# PWR.net
KiCad netlist of a schematic drawn in Altium Designer
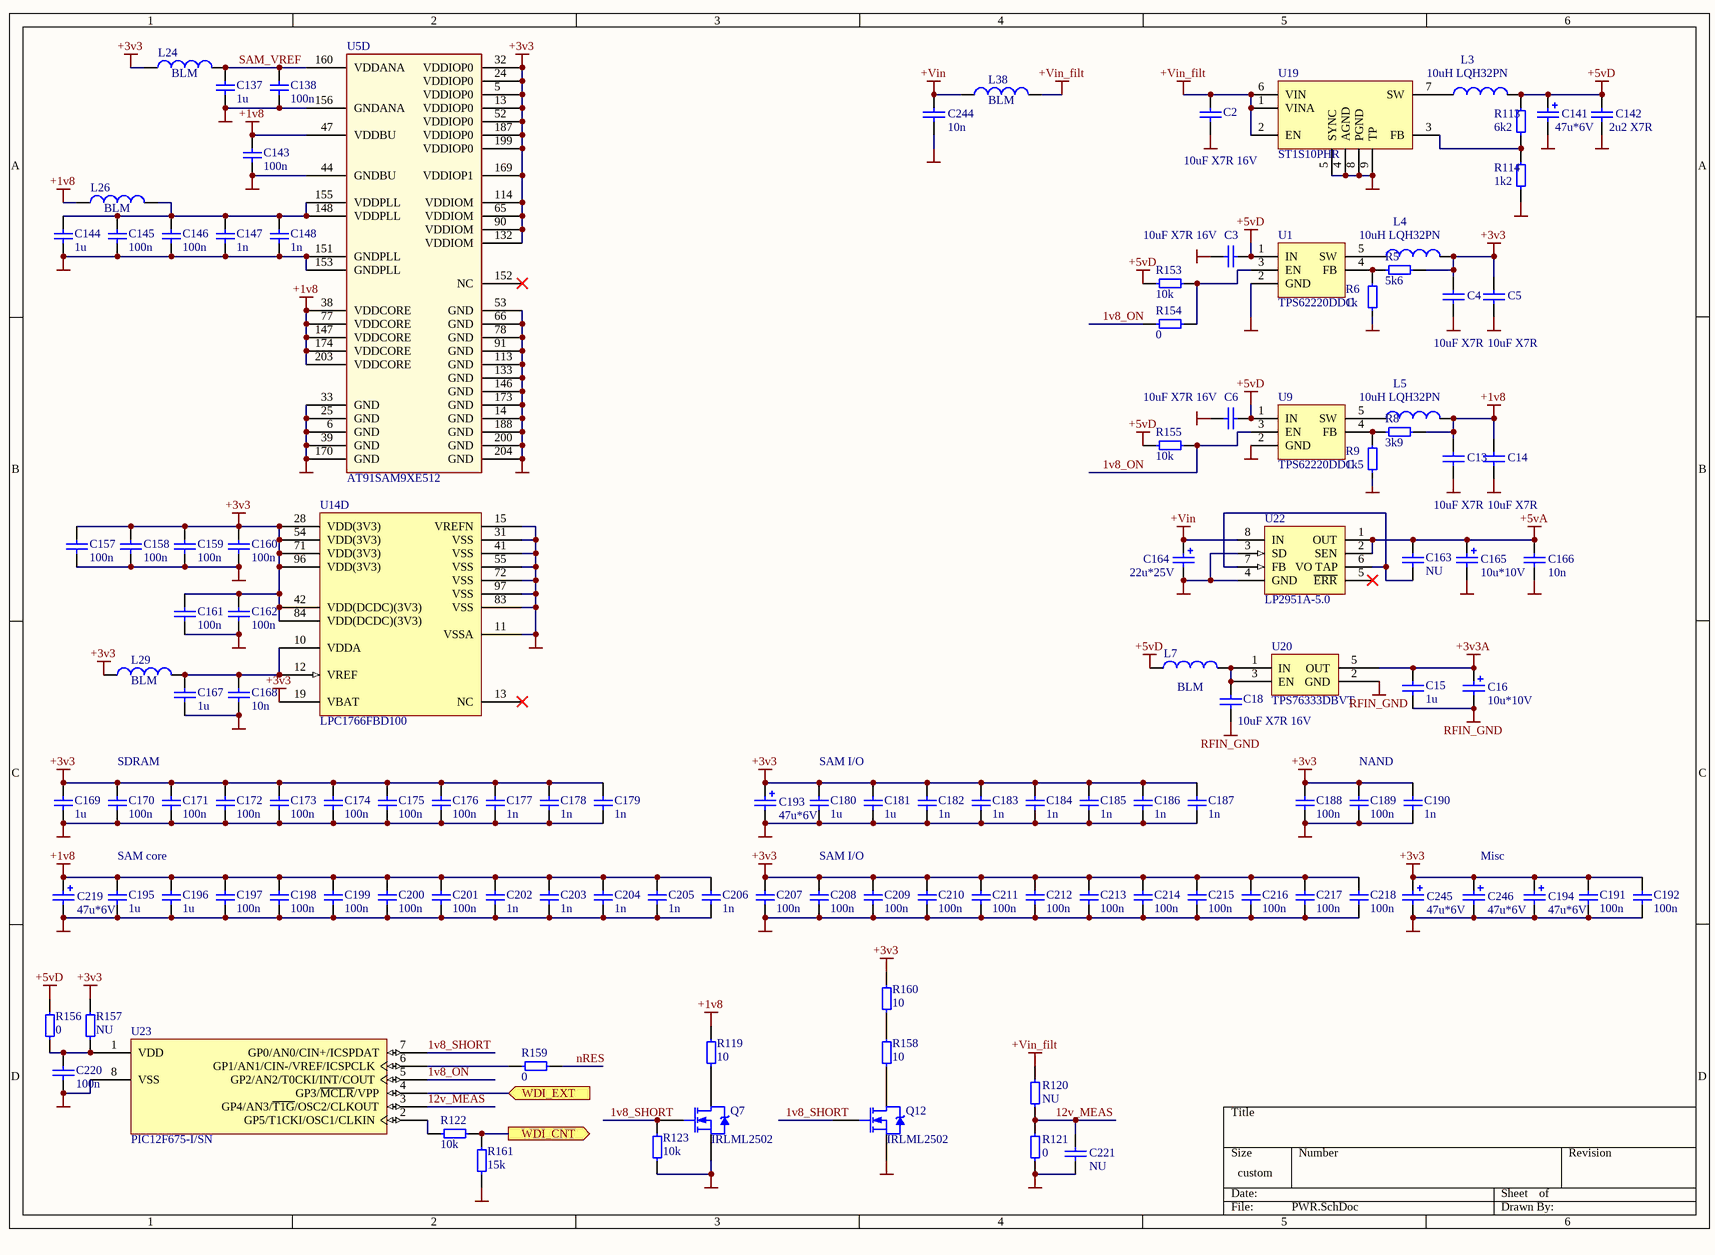
[diagram p0: PWR.SchDoc]

(export (version "E")
  (design (tool "Eeschema 10.0.6"))
  (components
    (comp (ref "C2")
      (value "10uF X7R 16V")
      (footprint "CAPC3216M")
      (description "Capacitor")
      (fields (field (name "PUBLISHER") "Altium Limited"))
      (libsource (lib "") (part "Cap_1"))
    )
    (comp (ref "C3")
      (value "10uF X7R 16V")
      (footprint "CAPC3216M")
      (description "Capacitor")
      (fields (field (name "PUBLISHER") "Altium Limited"))
      (libsource (lib "") (part "Cap_1"))
    )
    (comp (ref "C4")
      (value "10uF X7R")
      (footprint "CAPC3216M")
      (description "Capacitor")
      (fields (field (name "PUBLISHER") "Altium Limited"))
      (libsource (lib "") (part "Cap_1"))
    )
    (comp (ref "C5")
      (value "10uF X7R")
      (footprint "CAPC3216M")
      (description "Capacitor")
      (fields (field (name "PUBLISHER") "Altium Limited"))
      (libsource (lib "") (part "Cap_1"))
    )
    (comp (ref "C6")
      (value "10uF X7R 16V")
      (footprint "CAPC3216M")
      (description "Capacitor")
      (fields (field (name "PUBLISHER") "Altium Limited"))
      (libsource (lib "") (part "Cap_1"))
    )
    (comp (ref "C13")
      (value "10uF X7R")
      (footprint "CAPC3216M")
      (description "Capacitor")
      (fields (field (name "PUBLISHER") "Altium Limited"))
      (libsource (lib "") (part "Cap_1"))
    )
    (comp (ref "C14")
      (value "10uF X7R")
      (footprint "CAPC3216M")
      (description "Capacitor")
      (fields (field (name "PUBLISHER") "Altium Limited"))
      (libsource (lib "") (part "Cap_1"))
    )
    (comp (ref "C15")
      (value "1u")
      (footprint "CAPC2012L")
      (description "Capacitor")
      (fields (field (name "PUBLISHER") "Altium Limited"))
      (libsource (lib "") (part "Cap_1"))
    )
    (comp (ref "C16")
      (value "10u*10V")
      (footprint "Case_A")
      (description "Polarized Capacitor (Surface Mount)")
      (fields (field (name "PUBLISHER") "Altium Limited"))
      (libsource (lib "Sch components") (part "Cap Pol"))
    )
    (comp (ref "C18")
      (value "10uF X7R 16V")
      (footprint "CAPC3216M")
      (description "Capacitor")
      (fields (field (name "PUBLISHER") "Altium Limited"))
      (libsource (lib "") (part "Cap_1"))
    )
    (comp (ref "C137")
      (value "1u")
      (footprint "CAPC2012L")
      (description "Capacitor")
      (fields (field (name "PUBLISHER") "Altium Limited"))
      (libsource (lib "Sch components") (part "Cap"))
    )
    (comp (ref "C138")
      (value "100n")
      (footprint "CAPC1608L")
      (description "Capacitor")
      (fields (field (name "PUBLISHER") "Altium Limited"))
      (libsource (lib "Sch components") (part "Cap"))
    )
    (comp (ref "C141")
      (value "47u*6V")
      (footprint "Case_A")
      (description "Polarized Capacitor (Surface Mount)")
      (fields (field (name "PUBLISHER") "Altium Limited"))
      (libsource (lib "Sch components") (part "Cap Pol"))
    )
    (comp (ref "C142")
      (value "2u2 X7R")
      (footprint "CAPC2012N")
      (description "Capacitor")
      (fields (field (name "PUBLISHER") "Altium Limited"))
      (libsource (lib "") (part "Cap_1"))
    )
    (comp (ref "C143")
      (value "100n")
      (footprint "CAPC1608L")
      (description "Capacitor")
      (fields (field (name "PUBLISHER") "Altium Limited"))
      (libsource (lib "Sch components") (part "Cap"))
    )
    (comp (ref "C144")
      (value "1u")
      (footprint "CAPC2012L")
      (description "Capacitor")
      (fields (field (name "PUBLISHER") "Altium Limited"))
      (libsource (lib "Sch components") (part "Cap"))
    )
    (comp (ref "C145")
      (value "100n")
      (footprint "CAPC1608L")
      (description "Capacitor")
      (fields (field (name "PUBLISHER") "Altium Limited"))
      (libsource (lib "Sch components") (part "Cap"))
    )
    (comp (ref "C146")
      (value "100n")
      (footprint "CAPC1608L")
      (description "Capacitor")
      (fields (field (name "PUBLISHER") "Altium Limited"))
      (libsource (lib "Sch components") (part "Cap"))
    )
    (comp (ref "C147")
      (value "1n")
      (footprint "CAPC1608L")
      (description "Capacitor")
      (fields (field (name "PUBLISHER") "Altium Limited"))
      (libsource (lib "Sch components") (part "Cap"))
    )
    (comp (ref "C148")
      (value "1n")
      (footprint "CAPC1608L")
      (description "Capacitor")
      (fields (field (name "PUBLISHER") "Altium Limited"))
      (libsource (lib "Sch components") (part "Cap"))
    )
    (comp (ref "C157")
      (value "100n")
      (footprint "CAPC1608N")
      (description "Capacitor")
      (fields (field (name "PUBLISHER") "Altium Limited"))
      (libsource (lib "") (part "Cap_1"))
    )
    (comp (ref "C158")
      (value "100n")
      (footprint "CAPC1608N")
      (description "Capacitor")
      (fields (field (name "PUBLISHER") "Altium Limited"))
      (libsource (lib "") (part "Cap_1"))
    )
    (comp (ref "C159")
      (value "100n")
      (footprint "CAPC1608N")
      (description "Capacitor")
      (fields (field (name "PUBLISHER") "Altium Limited"))
      (libsource (lib "") (part "Cap_1"))
    )
    (comp (ref "C160")
      (value "100n")
      (footprint "CAPC1608N")
      (description "Capacitor")
      (fields (field (name "PUBLISHER") "Altium Limited"))
      (libsource (lib "") (part "Cap_1"))
    )
    (comp (ref "C161")
      (value "100n")
      (footprint "CAPC1608N")
      (description "Capacitor")
      (fields (field (name "PUBLISHER") "Altium Limited"))
      (libsource (lib "") (part "Cap_1"))
    )
    (comp (ref "C162")
      (value "100n")
      (footprint "CAPC1608N")
      (description "Capacitor")
      (fields (field (name "PUBLISHER") "Altium Limited"))
      (libsource (lib "") (part "Cap_1"))
    )
    (comp (ref "C163")
      (value "NU")
      (footprint "CAPC1608N")
      (description "Capacitor")
      (fields (field (name "PUBLISHER") "Altium Limited"))
      (libsource (lib "") (part "Cap_1"))
    )
    (comp (ref "C164")
      (value "22u*25V")
      (footprint "Case_D")
      (description "Polarized Capacitor (Surface Mount)")
      (fields (field (name "PUBLISHER") "Altium Limited"))
      (libsource (lib "Sch components") (part "Cap Pol"))
    )
    (comp (ref "C165")
      (value "10u*10V")
      (footprint "Case_A")
      (description "Polarized Capacitor (Surface Mount)")
      (fields (field (name "PUBLISHER") "Altium Limited"))
      (libsource (lib "Sch components") (part "Cap Pol"))
    )
    (comp (ref "C166")
      (value "10n")
      (footprint "CAPC1608N")
      (description "Capacitor")
      (fields (field (name "PUBLISHER") "Altium Limited"))
      (libsource (lib "") (part "Cap_1"))
    )
    (comp (ref "C167")
      (value "1u")
      (footprint "CAPC2012L")
      (description "Capacitor")
      (fields (field (name "PUBLISHER") "Altium Limited"))
      (libsource (lib "") (part "Cap_1"))
    )
    (comp (ref "C168")
      (value "10n")
      (footprint "CAPC1608N")
      (description "Capacitor")
      (fields (field (name "PUBLISHER") "Altium Limited"))
      (libsource (lib "") (part "Cap_1"))
    )
    (comp (ref "C169")
      (value "1u")
      (footprint "CAPC2012L")
      (description "Capacitor")
      (fields (field (name "PUBLISHER") "Altium Limited"))
      (libsource (lib "Sch components") (part "Cap"))
    )
    (comp (ref "C170")
      (value "100n")
      (footprint "CAPC1608L")
      (description "Capacitor")
      (fields (field (name "PUBLISHER") "Altium Limited"))
      (libsource (lib "Sch components") (part "Cap"))
    )
    (comp (ref "C171")
      (value "100n")
      (footprint "CAPC1608L")
      (description "Capacitor")
      (fields (field (name "PUBLISHER") "Altium Limited"))
      (libsource (lib "Sch components") (part "Cap"))
    )
    (comp (ref "C172")
      (value "100n")
      (footprint "CAPC1608L")
      (description "Capacitor")
      (fields (field (name "PUBLISHER") "Altium Limited"))
      (libsource (lib "Sch components") (part "Cap"))
    )
    (comp (ref "C173")
      (value "100n")
      (footprint "CAPC1608L")
      (description "Capacitor")
      (fields (field (name "PUBLISHER") "Altium Limited"))
      (libsource (lib "Sch components") (part "Cap"))
    )
    (comp (ref "C174")
      (value "100n")
      (footprint "CAPC1608L")
      (description "Capacitor")
      (fields (field (name "PUBLISHER") "Altium Limited"))
      (libsource (lib "Sch components") (part "Cap"))
    )
    (comp (ref "C175")
      (value "100n")
      (footprint "CAPC1608L")
      (description "Capacitor")
      (fields (field (name "PUBLISHER") "Altium Limited"))
      (libsource (lib "Sch components") (part "Cap"))
    )
    (comp (ref "C176")
      (value "100n")
      (footprint "CAPC1608L")
      (description "Capacitor")
      (fields (field (name "PUBLISHER") "Altium Limited"))
      (libsource (lib "Sch components") (part "Cap"))
    )
    (comp (ref "C177")
      (value "1n")
      (footprint "CAPC1608L")
      (description "Capacitor")
      (fields (field (name "PUBLISHER") "Altium Limited"))
      (libsource (lib "Sch components") (part "Cap"))
    )
    (comp (ref "C178")
      (value "1n")
      (footprint "CAPC1608L")
      (description "Capacitor")
      (fields (field (name "PUBLISHER") "Altium Limited"))
      (libsource (lib "Sch components") (part "Cap"))
    )
    (comp (ref "C179")
      (value "1n")
      (footprint "CAPC1608L")
      (description "Capacitor")
      (fields (field (name "PUBLISHER") "Altium Limited"))
      (libsource (lib "Sch components") (part "Cap"))
    )
    (comp (ref "C180")
      (value "1u")
      (footprint "CAPC2012L")
      (description "Capacitor")
      (fields (field (name "PUBLISHER") "Altium Limited"))
      (libsource (lib "Sch components") (part "Cap"))
    )
    (comp (ref "C181")
      (value "1u")
      (footprint "CAPC2012L")
      (description "Capacitor")
      (fields (field (name "PUBLISHER") "Altium Limited"))
      (libsource (lib "Sch components") (part "Cap"))
    )
    (comp (ref "C182")
      (value "1n")
      (footprint "CAPC1608L")
      (description "Capacitor")
      (fields (field (name "PUBLISHER") "Altium Limited"))
      (libsource (lib "Sch components") (part "Cap"))
    )
    (comp (ref "C183")
      (value "1n")
      (footprint "CAPC1608L")
      (description "Capacitor")
      (fields (field (name "PUBLISHER") "Altium Limited"))
      (libsource (lib "Sch components") (part "Cap"))
    )
    (comp (ref "C184")
      (value "1n")
      (footprint "CAPC1608L")
      (description "Capacitor")
      (fields (field (name "PUBLISHER") "Altium Limited"))
      (libsource (lib "Sch components") (part "Cap"))
    )
    (comp (ref "C185")
      (value "1n")
      (footprint "CAPC1608L")
      (description "Capacitor")
      (fields (field (name "PUBLISHER") "Altium Limited"))
      (libsource (lib "Sch components") (part "Cap"))
    )
    (comp (ref "C186")
      (value "1n")
      (footprint "CAPC1608L")
      (description "Capacitor")
      (fields (field (name "PUBLISHER") "Altium Limited"))
      (libsource (lib "Sch components") (part "Cap"))
    )
    (comp (ref "C187")
      (value "1n")
      (footprint "CAPC1608L")
      (description "Capacitor")
      (fields (field (name "PUBLISHER") "Altium Limited"))
      (libsource (lib "Sch components") (part "Cap"))
    )
    (comp (ref "C188")
      (value "100n")
      (footprint "CAPC1608L")
      (description "Capacitor")
      (fields (field (name "PUBLISHER") "Altium Limited"))
      (libsource (lib "Sch components") (part "Cap"))
    )
    (comp (ref "C189")
      (value "100n")
      (footprint "CAPC1608L")
      (description "Capacitor")
      (fields (field (name "PUBLISHER") "Altium Limited"))
      (libsource (lib "Sch components") (part "Cap"))
    )
    (comp (ref "C190")
      (value "1n")
      (footprint "CAPC1608L")
      (description "Capacitor")
      (fields (field (name "PUBLISHER") "Altium Limited"))
      (libsource (lib "Sch components") (part "Cap"))
    )
    (comp (ref "C191")
      (value "100n")
      (footprint "CAPC1608L")
      (description "Capacitor")
      (fields (field (name "PUBLISHER") "Altium Limited"))
      (libsource (lib "Sch components") (part "Cap"))
    )
    (comp (ref "C192")
      (value "100n")
      (footprint "CAPC1608L")
      (description "Capacitor")
      (fields (field (name "PUBLISHER") "Altium Limited"))
      (libsource (lib "Sch components") (part "Cap"))
    )
    (comp (ref "C193")
      (value "47u*6V")
      (footprint "Case_A")
      (description "Polarized Capacitor (Surface Mount)")
      (fields (field (name "PUBLISHER") "Altium Limited"))
      (libsource (lib "Sch components") (part "Cap Pol"))
    )
    (comp (ref "C194")
      (value "47u*6V")
      (footprint "Case_A")
      (description "Polarized Capacitor (Surface Mount)")
      (fields (field (name "PUBLISHER") "Altium Limited"))
      (libsource (lib "Sch components") (part "Cap Pol"))
    )
    (comp (ref "C195")
      (value "1u")
      (footprint "CAPC2012L")
      (description "Capacitor")
      (fields (field (name "PUBLISHER") "Altium Limited"))
      (libsource (lib "Sch components") (part "Cap"))
    )
    (comp (ref "C196")
      (value "1u")
      (footprint "CAPC2012L")
      (description "Capacitor")
      (fields (field (name "PUBLISHER") "Altium Limited"))
      (libsource (lib "Sch components") (part "Cap"))
    )
    (comp (ref "C197")
      (value "100n")
      (footprint "CAPC1608L")
      (description "Capacitor")
      (fields (field (name "PUBLISHER") "Altium Limited"))
      (libsource (lib "Sch components") (part "Cap"))
    )
    (comp (ref "C198")
      (value "100n")
      (footprint "CAPC1608L")
      (description "Capacitor")
      (fields (field (name "PUBLISHER") "Altium Limited"))
      (libsource (lib "Sch components") (part "Cap"))
    )
    (comp (ref "C199")
      (value "100n")
      (footprint "CAPC1608L")
      (description "Capacitor")
      (fields (field (name "PUBLISHER") "Altium Limited"))
      (libsource (lib "Sch components") (part "Cap"))
    )
    (comp (ref "C200")
      (value "100n")
      (footprint "CAPC1608L")
      (description "Capacitor")
      (fields (field (name "PUBLISHER") "Altium Limited"))
      (libsource (lib "Sch components") (part "Cap"))
    )
    (comp (ref "C201")
      (value "100n")
      (footprint "CAPC1608L")
      (description "Capacitor")
      (fields (field (name "PUBLISHER") "Altium Limited"))
      (libsource (lib "Sch components") (part "Cap"))
    )
    (comp (ref "C202")
      (value "1n")
      (footprint "CAPC1608L")
      (description "Capacitor")
      (fields (field (name "PUBLISHER") "Altium Limited"))
      (libsource (lib "Sch components") (part "Cap"))
    )
    (comp (ref "C203")
      (value "1n")
      (footprint "CAPC1608L")
      (description "Capacitor")
      (fields (field (name "PUBLISHER") "Altium Limited"))
      (libsource (lib "Sch components") (part "Cap"))
    )
    (comp (ref "C204")
      (value "1n")
      (footprint "CAPC1608L")
      (description "Capacitor")
      (fields (field (name "PUBLISHER") "Altium Limited"))
      (libsource (lib "Sch components") (part "Cap"))
    )
    (comp (ref "C205")
      (value "1n")
      (footprint "CAPC1608L")
      (description "Capacitor")
      (fields (field (name "PUBLISHER") "Altium Limited"))
      (libsource (lib "Sch components") (part "Cap"))
    )
    (comp (ref "C206")
      (value "1n")
      (footprint "CAPC1608L")
      (description "Capacitor")
      (fields (field (name "PUBLISHER") "Altium Limited"))
      (libsource (lib "Sch components") (part "Cap"))
    )
    (comp (ref "C207")
      (value "100n")
      (footprint "CAPC1608L")
      (description "Capacitor")
      (fields (field (name "PUBLISHER") "Altium Limited"))
      (libsource (lib "Sch components") (part "Cap"))
    )
    (comp (ref "C208")
      (value "100n")
      (footprint "CAPC1608L")
      (description "Capacitor")
      (fields (field (name "PUBLISHER") "Altium Limited"))
      (libsource (lib "Sch components") (part "Cap"))
    )
    (comp (ref "C209")
      (value "100n")
      (footprint "CAPC1608L")
      (description "Capacitor")
      (fields (field (name "PUBLISHER") "Altium Limited"))
      (libsource (lib "Sch components") (part "Cap"))
    )
    (comp (ref "C210")
      (value "100n")
      (footprint "CAPC1608L")
      (description "Capacitor")
      (fields (field (name "PUBLISHER") "Altium Limited"))
      (libsource (lib "Sch components") (part "Cap"))
    )
    (comp (ref "C211")
      (value "100n")
      (footprint "CAPC1608L")
      (description "Capacitor")
      (fields (field (name "PUBLISHER") "Altium Limited"))
      (libsource (lib "Sch components") (part "Cap"))
    )
    (comp (ref "C212")
      (value "100n")
      (footprint "CAPC1608L")
      (description "Capacitor")
      (fields (field (name "PUBLISHER") "Altium Limited"))
      (libsource (lib "Sch components") (part "Cap"))
    )
    (comp (ref "C213")
      (value "100n")
      (footprint "CAPC1608L")
      (description "Capacitor")
      (fields (field (name "PUBLISHER") "Altium Limited"))
      (libsource (lib "Sch components") (part "Cap"))
    )
    (comp (ref "C214")
      (value "100n")
      (footprint "CAPC1608L")
      (description "Capacitor")
      (fields (field (name "PUBLISHER") "Altium Limited"))
      (libsource (lib "Sch components") (part "Cap"))
    )
    (comp (ref "C215")
      (value "100n")
      (footprint "CAPC1608L")
      (description "Capacitor")
      (fields (field (name "PUBLISHER") "Altium Limited"))
      (libsource (lib "Sch components") (part "Cap"))
    )
    (comp (ref "C216")
      (value "100n")
      (footprint "CAPC1608L")
      (description "Capacitor")
      (fields (field (name "PUBLISHER") "Altium Limited"))
      (libsource (lib "Sch components") (part "Cap"))
    )
    (comp (ref "C217")
      (value "100n")
      (footprint "CAPC1608L")
      (description "Capacitor")
      (fields (field (name "PUBLISHER") "Altium Limited"))
      (libsource (lib "Sch components") (part "Cap"))
    )
    (comp (ref "C218")
      (value "100n")
      (footprint "CAPC1608L")
      (description "Capacitor")
      (fields (field (name "PUBLISHER") "Altium Limited"))
      (libsource (lib "Sch components") (part "Cap"))
    )
    (comp (ref "C219")
      (value "47u*6V")
      (footprint "Case_A")
      (description "Polarized Capacitor (Surface Mount)")
      (fields (field (name "PUBLISHER") "Altium Limited"))
      (libsource (lib "Sch components") (part "Cap Pol"))
    )
    (comp (ref "C220")
      (value "100n")
      (footprint "CAPC1608N")
      (description "Capacitor")
      (fields (field (name "PUBLISHER") "Altium Limited"))
      (libsource (lib "") (part "Cap_1"))
    )
    (comp (ref "C221")
      (value "NU")
      (footprint "CAPC1608N")
      (description "Capacitor")
      (fields (field (name "PUBLISHER") "Altium Limited"))
      (libsource (lib "") (part "Cap_1"))
    )
    (comp (ref "C244")
      (value "10n")
      (footprint "CAPC1608N")
      (description "Capacitor")
      (fields (field (name "PUBLISHER") "Altium Limited"))
      (libsource (lib "") (part "Cap_1"))
    )
    (comp (ref "C245")
      (value "47u*6V")
      (footprint "Case_A")
      (description "Polarized Capacitor (Surface Mount)")
      (fields (field (name "PUBLISHER") "Altium Limited"))
      (libsource (lib "Sch components") (part "Cap Pol"))
    )
    (comp (ref "C246")
      (value "47u*6V")
      (footprint "Case_A")
      (description "Polarized Capacitor (Surface Mount)")
      (fields (field (name "PUBLISHER") "Altium Limited"))
      (libsource (lib "Sch components") (part "Cap Pol"))
    )
    (comp (ref "L3")
      (value "10uH LQH32PN")
      (footprint "CAPC3225N")
      (libsource (lib "MyLibrary") (part "INDUCTOR"))
    )
    (comp (ref "L4")
      (value "10uH LQH32PN")
      (footprint "CAPC3225N")
      (libsource (lib "MyLibrary") (part "INDUCTOR"))
    )
    (comp (ref "L5")
      (value "10uH LQH32PN")
      (footprint "CAPC3225N")
      (libsource (lib "MyLibrary") (part "INDUCTOR"))
    )
    (comp (ref "L7")
      (value "BLM")
      (footprint "CAPC2012N")
      (description "Ferrite Bead")
      (fields (field (name "PUBLISHER") "Altium Limited"))
      (libsource (lib "") (part "Ferrite Bead_1"))
    )
    (comp (ref "L24")
      (value "BLM")
      (footprint "INDC2012L")
      (description "Inductor")
      (fields (field (name "PUBLISHER") "Altium Limited"))
      (libsource (lib "Sch components") (part "Inductor"))
    )
    (comp (ref "L26")
      (value "BLM")
      (footprint "INDC2012L")
      (description "Inductor")
      (fields (field (name "PUBLISHER") "Altium Limited"))
      (libsource (lib "Sch components") (part "Inductor"))
    )
    (comp (ref "L29")
      (value "BLM")
      (footprint "CAPC2012N")
      (description "Ferrite Bead")
      (fields (field (name "PUBLISHER") "Altium Limited"))
      (libsource (lib "Sch components") (part "Ferrite Bead"))
    )
    (comp (ref "L38")
      (value "BLM")
      (footprint "CAPC2012N")
      (description "Ferrite Bead")
      (fields (field (name "PUBLISHER") "Altium Limited"))
      (libsource (lib "Sch components") (part "Ferrite Bead"))
    )
    (comp (ref "Q7")
      (value "IRLML2502")
      (footprint "SOT-23")
      (description "HEXFET Power MOSFET")
      (fields (field (name "PUBLISHER") "Altium Limited"))
      (libsource (lib "IR Discrete MOSFET - Power") (part "IRLML2402"))
    )
    (comp (ref "Q12")
      (value "IRLML2502")
      (footprint "SOT-23")
      (description "HEXFET Power MOSFET")
      (fields (field (name "PUBLISHER") "Altium Limited"))
      (libsource (lib "IR Discrete MOSFET - Power") (part "IRLML2402"))
    )
    (comp (ref "R5")
      (value "5k6")
      (footprint "RESC1608L")
      (description "Resistor")
      (fields (field (name "PUBLISHER") "Altium Limited"))
      (libsource (lib "Sch components") (part "Res"))
    )
    (comp (ref "R6")
      (value "1k")
      (footprint "RESC1608L")
      (description "Resistor")
      (fields (field (name "PUBLISHER") "Altium Limited"))
      (libsource (lib "Sch components") (part "Res"))
    )
    (comp (ref "R8")
      (value "3k9")
      (footprint "RESC1608L")
      (description "Resistor")
      (fields (field (name "PUBLISHER") "Altium Limited"))
      (libsource (lib "Sch components") (part "Res"))
    )
    (comp (ref "R9")
      (value "1k5")
      (footprint "RESC1608L")
      (description "Resistor")
      (fields (field (name "PUBLISHER") "Altium Limited"))
      (libsource (lib "Sch components") (part "Res"))
    )
    (comp (ref "R113")
      (value "6k2")
      (footprint "RESC1608L")
      (description "Resistor")
      (fields (field (name "PUBLISHER") "Altium Limited"))
      (libsource (lib "Sch components") (part "Res"))
    )
    (comp (ref "R114")
      (value "1k2")
      (footprint "RESC1608L")
      (description "Resistor")
      (fields (field (name "PUBLISHER") "Altium Limited"))
      (libsource (lib "Sch components") (part "Res"))
    )
    (comp (ref "R119")
      (value "10")
      (footprint "RESC2012L")
      (description "Resistor")
      (fields (field (name "PUBLISHER") "Altium Limited"))
      (libsource (lib "Sch components") (part "Res"))
    )
    (comp (ref "R120")
      (value "NU")
      (footprint "RESC1608L")
      (description "Resistor")
      (fields (field (name "PUBLISHER") "Altium Limited"))
      (libsource (lib "Sch components") (part "Res"))
    )
    (comp (ref "R121")
      (value "0")
      (footprint "RESC1608L")
      (description "Resistor")
      (fields (field (name "PUBLISHER") "Altium Limited"))
      (libsource (lib "Sch components") (part "Res"))
    )
    (comp (ref "R122")
      (value "10k")
      (footprint "RESC1608L")
      (description "Resistor")
      (fields (field (name "PUBLISHER") "Altium Limited"))
      (libsource (lib "Sch components") (part "Res"))
    )
    (comp (ref "R123")
      (value "10k")
      (footprint "RESC1608L")
      (description "Resistor")
      (fields (field (name "PUBLISHER") "Altium Limited"))
      (libsource (lib "Sch components") (part "Res"))
    )
    (comp (ref "R153")
      (value "10k")
      (footprint "RESC1608L")
      (description "Resistor")
      (fields (field (name "PUBLISHER") "Altium Limited"))
      (libsource (lib "Sch components") (part "Res"))
    )
    (comp (ref "R154")
      (value "0")
      (footprint "RESC1608L")
      (description "Resistor")
      (fields (field (name "PUBLISHER") "Altium Limited"))
      (libsource (lib "Sch components") (part "Res"))
    )
    (comp (ref "R155")
      (value "10k")
      (footprint "RESC1608L")
      (description "Resistor")
      (fields (field (name "PUBLISHER") "Altium Limited"))
      (libsource (lib "Sch components") (part "Res"))
    )
    (comp (ref "R156")
      (value "0")
      (footprint "RESC1608L")
      (description "Resistor")
      (fields (field (name "PUBLISHER") "Altium Limited"))
      (libsource (lib "Sch components") (part "Res"))
    )
    (comp (ref "R157")
      (value "NU")
      (footprint "RESC1608L")
      (description "Resistor")
      (fields (field (name "PUBLISHER") "Altium Limited"))
      (libsource (lib "Sch components") (part "Res"))
    )
    (comp (ref "R158")
      (value "10")
      (footprint "RESC2012L")
      (description "Resistor")
      (fields (field (name "PUBLISHER") "Altium Limited"))
      (libsource (lib "Sch components") (part "Res"))
    )
    (comp (ref "R159")
      (value "0")
      (footprint "RESC1608L")
      (description "Resistor")
      (fields (field (name "PUBLISHER") "Altium Limited"))
      (libsource (lib "Sch components") (part "Res"))
    )
    (comp (ref "R160")
      (value "10")
      (footprint "RESC2012L")
      (description "Resistor")
      (fields (field (name "PUBLISHER") "Altium Limited"))
      (libsource (lib "Sch components") (part "Res"))
    )
    (comp (ref "R161")
      (value "15k")
      (footprint "RESC1608L")
      (description "Resistor")
      (fields (field (name "PUBLISHER") "Altium Limited"))
      (libsource (lib "Sch components") (part "Res"))
    )
    (comp (ref "U1")
      (value "TPS62220DDC")
      (footprint "SOT95P280X160-5L MO-193AB")
      (description "1.8V 300mA SW regulator")
      (libsource (lib "Sch components") (part "TPS6202"))
    )
    (comp (ref "U5")
      (value "AT91SAM9XE512")
      (footprint "SQFP50P3120X3120-208N")
      (libsource (lib "MyWLib") (part "AT91SAM9XE512"))
    )
    (comp (ref "U9")
      (value "TPS62220DDC")
      (footprint "SOT95P280X160-5L MO-193AB")
      (description "1.8V 300mA SW regulator")
      (libsource (lib "Sch components") (part "TPS6202"))
    )
    (comp (ref "U14")
      (value "LPC1766FBD100")
      (footprint "SOT407-1_L")
      (fields (field (name "PUBLISHER") "Altium Limited"))
      (libsource (lib "MyWLib") (part "LPC1766FBD100"))
    )
    (comp (ref "U19")
      (value "ST1S10PHR")
      (footprint "SOIC127P600X170_HS-8N")
      (description "3 A, 900 kHz, synchronous step-down regulator")
      (libsource (lib "Sch components") (part "ST1S10"))
    )
    (comp (ref "U20")
      (value "TPS76333DBVT")
      (footprint "SOT95P280X160-5L MO-193AB")
      (description "1.8 V 150 mA low-dropout linear regulator")
      (libsource (lib "Sch components") (part "TPS76318"))
    )
    (comp (ref "U22")
      (value "LP2951A-5.0")
      (footprint "M08A_L")
      (description "MicroPower Voltage Regulator")
      (fields (field (name "PUBLISHER") "Altium Limited"))
      (libsource (lib "ON Semi Power Mgt Voltage Regulator") (part "LP2951ACDMR2"))
    )
    (comp (ref "U23")
      (value "PIC12F675-I/SN")
      (footprint "SOIC-SN8_N")
      (description "FLASH-Based 8-Bit CMOS Microcontroller, 10-Bit A/D, 8-Pin SOIC 150mil, Industrial Temperature")
      (fields (field (name "PUBLISHER") "Altium Limited"))
      (libsource (lib "Microchip Microcontroller 8-Bit PIC12") (part "PIC12F675-I/SN"))
    )
  )
  (nets
    (net (code "1") (name "+1v8") (class "Default")
      (node (ref "C13") (pin "2") (pinfunction "2_2") (pintype "passive"))
      (node (ref "C14") (pin "2") (pinfunction "2_2") (pintype "passive"))
      (node (ref "C143") (pin "2") (pinfunction "2_2") (pintype "passive"))
      (node (ref "C195") (pin "2") (pinfunction "2_2") (pintype "passive"))
      (node (ref "C196") (pin "2") (pinfunction "2_2") (pintype "passive"))
      (node (ref "C197") (pin "2") (pinfunction "2_2") (pintype "passive"))
      (node (ref "C198") (pin "2") (pinfunction "2_2") (pintype "passive"))
      (node (ref "C199") (pin "2") (pinfunction "2_2") (pintype "passive"))
      (node (ref "C200") (pin "2") (pinfunction "2_2") (pintype "passive"))
      (node (ref "C201") (pin "2") (pinfunction "2_2") (pintype "passive"))
      (node (ref "C202") (pin "2") (pinfunction "2_2") (pintype "passive"))
      (node (ref "C203") (pin "2") (pinfunction "2_2") (pintype "passive"))
      (node (ref "C204") (pin "2") (pinfunction "2_2") (pintype "passive"))
      (node (ref "C205") (pin "2") (pinfunction "2_2") (pintype "passive"))
      (node (ref "C206") (pin "2") (pinfunction "2_2") (pintype "passive"))
      (node (ref "C219") (pin "1") (pinfunction "1_1") (pintype "passive"))
      (node (ref "L26") (pin "1") (pinfunction "1_1") (pintype "passive"))
      (node (ref "L5") (pin "2") (pinfunction "2_2") (pintype "passive"))
      (node (ref "R119") (pin "2") (pinfunction "2_2") (pintype "passive"))
      (node (ref "R8") (pin "1") (pinfunction "1_1") (pintype "passive"))
      (node (ref "U5") (pin "147") (pinfunction "VDDCORE_147") (pintype "passive"))
      (node (ref "U5") (pin "174") (pinfunction "VDDCORE_174") (pintype "passive"))
      (node (ref "U5") (pin "203") (pinfunction "VDDCORE_203") (pintype "passive"))
      (node (ref "U5") (pin "38") (pinfunction "VDDCORE_38") (pintype "passive"))
      (node (ref "U5") (pin "47") (pinfunction "VDDBU_47") (pintype "passive"))
      (node (ref "U5") (pin "77") (pinfunction "VDDCORE_77") (pintype "passive"))
    )
    (net (code "2") (name "+3v3") (class "Default")
      (node (ref "C157") (pin "2") (pinfunction "2_2") (pintype "passive"))
      (node (ref "C158") (pin "2") (pinfunction "2_2") (pintype "passive"))
      (node (ref "C159") (pin "2") (pinfunction "2_2") (pintype "passive"))
      (node (ref "C160") (pin "2") (pinfunction "2_2") (pintype "passive"))
      (node (ref "C161") (pin "2") (pinfunction "2_2") (pintype "passive"))
      (node (ref "C162") (pin "2") (pinfunction "2_2") (pintype "passive"))
      (node (ref "C169") (pin "2") (pinfunction "2_2") (pintype "passive"))
      (node (ref "C170") (pin "2") (pinfunction "2_2") (pintype "passive"))
      (node (ref "C171") (pin "2") (pinfunction "2_2") (pintype "passive"))
      (node (ref "C172") (pin "2") (pinfunction "2_2") (pintype "passive"))
      (node (ref "C173") (pin "2") (pinfunction "2_2") (pintype "passive"))
      (node (ref "C174") (pin "2") (pinfunction "2_2") (pintype "passive"))
      (node (ref "C175") (pin "2") (pinfunction "2_2") (pintype "passive"))
      (node (ref "C176") (pin "2") (pinfunction "2_2") (pintype "passive"))
      (node (ref "C177") (pin "2") (pinfunction "2_2") (pintype "passive"))
      (node (ref "C178") (pin "2") (pinfunction "2_2") (pintype "passive"))
      (node (ref "C179") (pin "2") (pinfunction "2_2") (pintype "passive"))
      (node (ref "C180") (pin "2") (pinfunction "2_2") (pintype "passive"))
      (node (ref "C181") (pin "2") (pinfunction "2_2") (pintype "passive"))
      (node (ref "C182") (pin "2") (pinfunction "2_2") (pintype "passive"))
      (node (ref "C183") (pin "2") (pinfunction "2_2") (pintype "passive"))
      (node (ref "C184") (pin "2") (pinfunction "2_2") (pintype "passive"))
      (node (ref "C185") (pin "2") (pinfunction "2_2") (pintype "passive"))
      (node (ref "C186") (pin "2") (pinfunction "2_2") (pintype "passive"))
      (node (ref "C187") (pin "2") (pinfunction "2_2") (pintype "passive"))
      (node (ref "C188") (pin "2") (pinfunction "2_2") (pintype "passive"))
      (node (ref "C189") (pin "2") (pinfunction "2_2") (pintype "passive"))
      (node (ref "C190") (pin "2") (pinfunction "2_2") (pintype "passive"))
      (node (ref "C191") (pin "2") (pinfunction "2_2") (pintype "passive"))
      (node (ref "C192") (pin "2") (pinfunction "2_2") (pintype "passive"))
      (node (ref "C193") (pin "1") (pinfunction "1_1") (pintype "passive"))
      (node (ref "C194") (pin "1") (pinfunction "1_1") (pintype "passive"))
      (node (ref "C207") (pin "2") (pinfunction "2_2") (pintype "passive"))
      (node (ref "C208") (pin "2") (pinfunction "2_2") (pintype "passive"))
      (node (ref "C209") (pin "2") (pinfunction "2_2") (pintype "passive"))
      (node (ref "C210") (pin "2") (pinfunction "2_2") (pintype "passive"))
      (node (ref "C211") (pin "2") (pinfunction "2_2") (pintype "passive"))
      (node (ref "C212") (pin "2") (pinfunction "2_2") (pintype "passive"))
      (node (ref "C213") (pin "2") (pinfunction "2_2") (pintype "passive"))
      (node (ref "C214") (pin "2") (pinfunction "2_2") (pintype "passive"))
      (node (ref "C215") (pin "2") (pinfunction "2_2") (pintype "passive"))
      (node (ref "C216") (pin "2") (pinfunction "2_2") (pintype "passive"))
      (node (ref "C217") (pin "2") (pinfunction "2_2") (pintype "passive"))
      (node (ref "C218") (pin "2") (pinfunction "2_2") (pintype "passive"))
      (node (ref "C245") (pin "1") (pinfunction "1_1") (pintype "passive"))
      (node (ref "C246") (pin "1") (pinfunction "1_1") (pintype "passive"))
      (node (ref "C4") (pin "2") (pinfunction "2_2") (pintype "passive"))
      (node (ref "C5") (pin "2") (pinfunction "2_2") (pintype "passive"))
      (node (ref "L24") (pin "1") (pinfunction "1_1") (pintype "passive"))
      (node (ref "L29") (pin "1") (pinfunction "1_1") (pintype "passive"))
      (node (ref "L4") (pin "2") (pinfunction "2_2") (pintype "passive"))
      (node (ref "R157") (pin "2") (pinfunction "2_2") (pintype "passive"))
      (node (ref "R160") (pin "2") (pinfunction "2_2") (pintype "passive"))
      (node (ref "R5") (pin "1") (pinfunction "1_1") (pintype "passive"))
      (node (ref "U14") (pin "19") (pinfunction "VBAT_19") (pintype "power_in"))
      (node (ref "U14") (pin "28") (pinfunction "VDD(3V3)_28") (pintype "power_in"))
      (node (ref "U14") (pin "42") (pinfunction "VDD(DCDC)(3V3)_42") (pintype "power_in"))
      (node (ref "U14") (pin "54") (pinfunction "VDD(3V3)_54") (pintype "power_in"))
      (node (ref "U14") (pin "71") (pinfunction "VDD(3V3)_71") (pintype "power_in"))
      (node (ref "U14") (pin "84") (pinfunction "VDD(DCDC)(3V3)_84") (pintype "power_in"))
      (node (ref "U14") (pin "96") (pinfunction "VDD(3V3)_96") (pintype "power_in"))
      (node (ref "U5") (pin "114") (pinfunction "VDDIOM_114") (pintype "passive"))
      (node (ref "U5") (pin "13") (pinfunction "VDDIOP0_13") (pintype "passive"))
      (node (ref "U5") (pin "132") (pinfunction "VDDIOM_132") (pintype "passive"))
      (node (ref "U5") (pin "169") (pinfunction "VDDIOP1_169") (pintype "passive"))
      (node (ref "U5") (pin "187") (pinfunction "VDDIOP0_187") (pintype "passive"))
      (node (ref "U5") (pin "199") (pinfunction "VDDIOP0_199") (pintype "passive"))
      (node (ref "U5") (pin "24") (pinfunction "VDDIOP0_24") (pintype "passive"))
      (node (ref "U5") (pin "32") (pinfunction "VDDIOP0_32") (pintype "passive"))
      (node (ref "U5") (pin "5") (pinfunction "VDDIOP0_5") (pintype "passive"))
      (node (ref "U5") (pin "52") (pinfunction "VDDIOP0_52") (pintype "passive"))
      (node (ref "U5") (pin "65") (pinfunction "VDDIOM_65") (pintype "passive"))
      (node (ref "U5") (pin "90") (pinfunction "VDDIOM_90") (pintype "passive"))
    )
    (net (code "3") (name "+3v3A") (class "Default")
      (node (ref "C15") (pin "1") (pinfunction "1_1") (pintype "passive"))
      (node (ref "C16") (pin "1") (pinfunction "1_1") (pintype "passive"))
      (node (ref "U20") (pin "5") (pinfunction "OUT_5") (pintype "passive"))
    )
    (net (code "4") (name "+5vA") (class "Default")
      (node (ref "C163") (pin "1") (pinfunction "1_1") (pintype "passive"))
      (node (ref "C165") (pin "1") (pinfunction "1_1") (pintype "passive"))
      (node (ref "C166") (pin "2") (pinfunction "2_2") (pintype "passive"))
      (node (ref "U22") (pin "1") (pinfunction "OUT_1") (pintype "power_in"))
      (node (ref "U22") (pin "2") (pinfunction "SEN_2") (pintype "passive"))
    )
    (net (code "5") (name "+5vD") (class "Default")
      (node (ref "C141") (pin "1") (pinfunction "1_1") (pintype "passive"))
      (node (ref "C142") (pin "2") (pinfunction "2_2") (pintype "passive"))
      (node (ref "C3") (pin "2") (pinfunction "2_2") (pintype "passive"))
      (node (ref "C6") (pin "2") (pinfunction "2_2") (pintype "passive"))
      (node (ref "L3") (pin "2") (pinfunction "2_2") (pintype "passive"))
      (node (ref "L7") (pin "2") (pinfunction "2_2") (pintype "passive"))
      (node (ref "R113") (pin "2") (pinfunction "2_2") (pintype "passive"))
      (node (ref "R153") (pin "1") (pinfunction "1_1") (pintype "passive"))
      (node (ref "R155") (pin "1") (pinfunction "1_1") (pintype "passive"))
      (node (ref "R156") (pin "2") (pinfunction "2_2") (pintype "passive"))
      (node (ref "U1") (pin "1") (pinfunction "IN_1") (pintype "passive"))
      (node (ref "U9") (pin "1") (pinfunction "IN_1") (pintype "passive"))
    )
    (net (code "6") (name "+Vin") (class "Default")
      (node (ref "C164") (pin "1") (pinfunction "1_1") (pintype "passive"))
      (node (ref "C244") (pin "2") (pinfunction "2_2") (pintype "passive"))
      (node (ref "L38") (pin "1") (pinfunction "1_1") (pintype "passive"))
      (node (ref "U22") (pin "8") (pinfunction "IN_8") (pintype "power_in"))
    )
    (net (code "7") (name "+Vin_filt") (class "Default")
      (node (ref "C2") (pin "2") (pinfunction "2_2") (pintype "passive"))
      (node (ref "L38") (pin "2") (pinfunction "2_2") (pintype "passive"))
      (node (ref "R120") (pin "2") (pinfunction "2_2") (pintype "passive"))
      (node (ref "U19") (pin "1") (pinfunction "VINA_1") (pintype "passive"))
      (node (ref "U19") (pin "2") (pinfunction "EN_2") (pintype "passive"))
      (node (ref "U19") (pin "6") (pinfunction "VIN_6") (pintype "passive"))
    )
    (net (code "8") (name "/1v8_ON") (class "Default")
      (node (ref "R154") (pin "2") (pinfunction "2_2") (pintype "passive"))
      (node (ref "R155") (pin "2") (pinfunction "2_2") (pintype "passive"))
      (node (ref "U23") (pin "5") (pinfunction "GP2/AN2/T0CKI/INT/COUT_5") (pintype "bidirectional"))
      (node (ref "U9") (pin "3") (pinfunction "EN_3") (pintype "passive"))
    )
    (net (code "9") (name "/1v8_SHORT") (class "Default")
      (node (ref "Q12") (pin "1") (pinfunction "G_1") (pintype "passive"))
      (node (ref "Q7") (pin "1") (pinfunction "G_1") (pintype "passive"))
      (node (ref "R123") (pin "2") (pinfunction "2_2") (pintype "passive"))
      (node (ref "U23") (pin "7") (pinfunction "GP0/AN0/CIN+/ICSPDAT_7") (pintype "bidirectional"))
    )
    (net (code "10") (name "/12v_MEAS") (class "Default")
      (node (ref "C221") (pin "2") (pinfunction "2_2") (pintype "passive"))
      (node (ref "R120") (pin "1") (pinfunction "1_1") (pintype "passive"))
      (node (ref "R121") (pin "2") (pinfunction "2_2") (pintype "passive"))
      (node (ref "U23") (pin "3") (pinfunction "GP4/AN3/~{T1G}/OSC2/CLKOUT_3") (pintype "bidirectional"))
    )
    (net (code "11") (name "/SAM_VREF") (class "Default")
      (node (ref "C137") (pin "2") (pinfunction "2_2") (pintype "passive"))
      (node (ref "C138") (pin "2") (pinfunction "2_2") (pintype "passive"))
      (node (ref "L24") (pin "2") (pinfunction "2_2") (pintype "passive"))
      (node (ref "U5") (pin "160") (pinfunction "VDDANA_160") (pintype "passive"))
    )
    (net (code "12") (name "/WDI_CNT") (class "Default")
      (node (ref "R122") (pin "2") (pinfunction "2_2") (pintype "passive"))
      (node (ref "R161") (pin "2") (pinfunction "2_2") (pintype "passive"))
    )
    (net (code "13") (name "/WDI_EXT") (class "Default")
      (node (ref "U23") (pin "4") (pinfunction "GP3/~{MCLR}/VPP_4") (pintype "bidirectional"))
    )
    (net (code "14") (name "/nRES") (class "Default")
      (node (ref "R159") (pin "1") (pinfunction "1_1") (pintype "passive"))
    )
    (net (code "15") (name "GND") (class "Default")
      (node (ref "C13") (pin "1") (pinfunction "1_1") (pintype "passive"))
      (node (ref "C137") (pin "1") (pinfunction "1_1") (pintype "passive"))
      (node (ref "C138") (pin "1") (pinfunction "1_1") (pintype "passive"))
      (node (ref "C14") (pin "1") (pinfunction "1_1") (pintype "passive"))
      (node (ref "C141") (pin "2") (pinfunction "2_2") (pintype "passive"))
      (node (ref "C142") (pin "1") (pinfunction "1_1") (pintype "passive"))
      (node (ref "C143") (pin "1") (pinfunction "1_1") (pintype "passive"))
      (node (ref "C144") (pin "1") (pinfunction "1_1") (pintype "passive"))
      (node (ref "C145") (pin "1") (pinfunction "1_1") (pintype "passive"))
      (node (ref "C146") (pin "1") (pinfunction "1_1") (pintype "passive"))
      (node (ref "C147") (pin "1") (pinfunction "1_1") (pintype "passive"))
      (node (ref "C148") (pin "1") (pinfunction "1_1") (pintype "passive"))
      (node (ref "C157") (pin "1") (pinfunction "1_1") (pintype "passive"))
      (node (ref "C158") (pin "1") (pinfunction "1_1") (pintype "passive"))
      (node (ref "C159") (pin "1") (pinfunction "1_1") (pintype "passive"))
      (node (ref "C160") (pin "1") (pinfunction "1_1") (pintype "passive"))
      (node (ref "C161") (pin "1") (pinfunction "1_1") (pintype "passive"))
      (node (ref "C162") (pin "1") (pinfunction "1_1") (pintype "passive"))
      (node (ref "C164") (pin "2") (pinfunction "2_2") (pintype "passive"))
      (node (ref "C165") (pin "2") (pinfunction "2_2") (pintype "passive"))
      (node (ref "C166") (pin "1") (pinfunction "1_1") (pintype "passive"))
      (node (ref "C167") (pin "1") (pinfunction "1_1") (pintype "passive"))
      (node (ref "C168") (pin "1") (pinfunction "1_1") (pintype "passive"))
      (node (ref "C169") (pin "1") (pinfunction "1_1") (pintype "passive"))
      (node (ref "C170") (pin "1") (pinfunction "1_1") (pintype "passive"))
      (node (ref "C171") (pin "1") (pinfunction "1_1") (pintype "passive"))
      (node (ref "C172") (pin "1") (pinfunction "1_1") (pintype "passive"))
      (node (ref "C173") (pin "1") (pinfunction "1_1") (pintype "passive"))
      (node (ref "C174") (pin "1") (pinfunction "1_1") (pintype "passive"))
      (node (ref "C175") (pin "1") (pinfunction "1_1") (pintype "passive"))
      (node (ref "C176") (pin "1") (pinfunction "1_1") (pintype "passive"))
      (node (ref "C177") (pin "1") (pinfunction "1_1") (pintype "passive"))
      (node (ref "C178") (pin "1") (pinfunction "1_1") (pintype "passive"))
      (node (ref "C179") (pin "1") (pinfunction "1_1") (pintype "passive"))
      (node (ref "C180") (pin "1") (pinfunction "1_1") (pintype "passive"))
      (node (ref "C181") (pin "1") (pinfunction "1_1") (pintype "passive"))
      (node (ref "C182") (pin "1") (pinfunction "1_1") (pintype "passive"))
      (node (ref "C183") (pin "1") (pinfunction "1_1") (pintype "passive"))
      (node (ref "C184") (pin "1") (pinfunction "1_1") (pintype "passive"))
      (node (ref "C185") (pin "1") (pinfunction "1_1") (pintype "passive"))
      (node (ref "C186") (pin "1") (pinfunction "1_1") (pintype "passive"))
      (node (ref "C187") (pin "1") (pinfunction "1_1") (pintype "passive"))
      (node (ref "C188") (pin "1") (pinfunction "1_1") (pintype "passive"))
      (node (ref "C189") (pin "1") (pinfunction "1_1") (pintype "passive"))
      (node (ref "C190") (pin "1") (pinfunction "1_1") (pintype "passive"))
      (node (ref "C191") (pin "1") (pinfunction "1_1") (pintype "passive"))
      (node (ref "C192") (pin "1") (pinfunction "1_1") (pintype "passive"))
      (node (ref "C193") (pin "2") (pinfunction "2_2") (pintype "passive"))
      (node (ref "C194") (pin "2") (pinfunction "2_2") (pintype "passive"))
      (node (ref "C195") (pin "1") (pinfunction "1_1") (pintype "passive"))
      (node (ref "C196") (pin "1") (pinfunction "1_1") (pintype "passive"))
      (node (ref "C197") (pin "1") (pinfunction "1_1") (pintype "passive"))
      (node (ref "C198") (pin "1") (pinfunction "1_1") (pintype "passive"))
      (node (ref "C199") (pin "1") (pinfunction "1_1") (pintype "passive"))
      (node (ref "C2") (pin "1") (pinfunction "1_1") (pintype "passive"))
      (node (ref "C200") (pin "1") (pinfunction "1_1") (pintype "passive"))
      (node (ref "C201") (pin "1") (pinfunction "1_1") (pintype "passive"))
      (node (ref "C202") (pin "1") (pinfunction "1_1") (pintype "passive"))
      (node (ref "C203") (pin "1") (pinfunction "1_1") (pintype "passive"))
      (node (ref "C204") (pin "1") (pinfunction "1_1") (pintype "passive"))
      (node (ref "C205") (pin "1") (pinfunction "1_1") (pintype "passive"))
      (node (ref "C206") (pin "1") (pinfunction "1_1") (pintype "passive"))
      (node (ref "C207") (pin "1") (pinfunction "1_1") (pintype "passive"))
      (node (ref "C208") (pin "1") (pinfunction "1_1") (pintype "passive"))
      (node (ref "C209") (pin "1") (pinfunction "1_1") (pintype "passive"))
      (node (ref "C210") (pin "1") (pinfunction "1_1") (pintype "passive"))
      (node (ref "C211") (pin "1") (pinfunction "1_1") (pintype "passive"))
      (node (ref "C212") (pin "1") (pinfunction "1_1") (pintype "passive"))
      (node (ref "C213") (pin "1") (pinfunction "1_1") (pintype "passive"))
      (node (ref "C214") (pin "1") (pinfunction "1_1") (pintype "passive"))
      (node (ref "C215") (pin "1") (pinfunction "1_1") (pintype "passive"))
      (node (ref "C216") (pin "1") (pinfunction "1_1") (pintype "passive"))
      (node (ref "C217") (pin "1") (pinfunction "1_1") (pintype "passive"))
      (node (ref "C218") (pin "1") (pinfunction "1_1") (pintype "passive"))
      (node (ref "C219") (pin "2") (pinfunction "2_2") (pintype "passive"))
      (node (ref "C220") (pin "1") (pinfunction "1_1") (pintype "passive"))
      (node (ref "C221") (pin "1") (pinfunction "1_1") (pintype "passive"))
      (node (ref "C244") (pin "1") (pinfunction "1_1") (pintype "passive"))
      (node (ref "C245") (pin "2") (pinfunction "2_2") (pintype "passive"))
      (node (ref "C246") (pin "2") (pinfunction "2_2") (pintype "passive"))
      (node (ref "C3") (pin "1") (pinfunction "1_1") (pintype "passive"))
      (node (ref "C4") (pin "1") (pinfunction "1_1") (pintype "passive"))
      (node (ref "C5") (pin "1") (pinfunction "1_1") (pintype "passive"))
      (node (ref "C6") (pin "1") (pinfunction "1_1") (pintype "passive"))
      (node (ref "Q12") (pin "2") (pinfunction "S_2") (pintype "passive"))
      (node (ref "Q7") (pin "2") (pinfunction "S_2") (pintype "passive"))
      (node (ref "R114") (pin "1") (pinfunction "1_1") (pintype "passive"))
      (node (ref "R121") (pin "1") (pinfunction "1_1") (pintype "passive"))
      (node (ref "R123") (pin "1") (pinfunction "1_1") (pintype "passive"))
      (node (ref "R161") (pin "1") (pinfunction "1_1") (pintype "passive"))
      (node (ref "R6") (pin "1") (pinfunction "1_1") (pintype "passive"))
      (node (ref "R9") (pin "1") (pinfunction "1_1") (pintype "passive"))
      (node (ref "U1") (pin "2") (pinfunction "GND_2") (pintype "passive"))
      (node (ref "U14") (pin "11") (pinfunction "VSSA_11") (pintype "power_in"))
      (node (ref "U14") (pin "15") (pinfunction "VREFN_15") (pintype "power_in"))
      (node (ref "U14") (pin "31") (pinfunction "VSS_31") (pintype "power_in"))
      (node (ref "U14") (pin "41") (pinfunction "VSS_41") (pintype "power_in"))
      (node (ref "U14") (pin "55") (pinfunction "VSS_55") (pintype "power_in"))
      (node (ref "U14") (pin "72") (pinfunction "VSS_72") (pintype "power_in"))
      (node (ref "U14") (pin "83") (pinfunction "VSS_83") (pintype "power_in"))
      (node (ref "U14") (pin "97") (pinfunction "VSS_97") (pintype "power_in"))
      (node (ref "U19") (pin "4") (pinfunction "AGND_4") (pintype "passive"))
      (node (ref "U19") (pin "5") (pinfunction "SYNC_5") (pintype "passive"))
      (node (ref "U19") (pin "8") (pinfunction "PGND_8") (pintype "passive"))
      (node (ref "U19") (pin "9") (pinfunction "TP_9") (pintype "passive"))
      (node (ref "U22") (pin "3") (pinfunction "SD_3") (pintype "input"))
      (node (ref "U22") (pin "4") (pinfunction "GND_4") (pintype "power_in"))
      (node (ref "U23") (pin "8") (pinfunction "VSS_8") (pintype "power_in"))
      (node (ref "U5") (pin "113") (pinfunction "GND_113") (pintype "passive"))
      (node (ref "U5") (pin "133") (pinfunction "GND_133") (pintype "passive"))
      (node (ref "U5") (pin "14") (pinfunction "GND_14") (pintype "passive"))
      (node (ref "U5") (pin "146") (pinfunction "GND_146") (pintype "passive"))
      (node (ref "U5") (pin "151") (pinfunction "GNDPLL_151") (pintype "passive"))
      (node (ref "U5") (pin "153") (pinfunction "GNDPLL_153") (pintype "passive"))
      (node (ref "U5") (pin "156") (pinfunction "GNDANA_156") (pintype "passive"))
      (node (ref "U5") (pin "170") (pinfunction "GND_170") (pintype "passive"))
      (node (ref "U5") (pin "173") (pinfunction "GND_173") (pintype "passive"))
      (node (ref "U5") (pin "188") (pinfunction "GND_188") (pintype "passive"))
      (node (ref "U5") (pin "200") (pinfunction "GND_200") (pintype "passive"))
      (node (ref "U5") (pin "204") (pinfunction "GND_204") (pintype "passive"))
      (node (ref "U5") (pin "25") (pinfunction "GND_25") (pintype "passive"))
      (node (ref "U5") (pin "33") (pinfunction "GND_33") (pintype "passive"))
      (node (ref "U5") (pin "39") (pinfunction "GND_39") (pintype "passive"))
      (node (ref "U5") (pin "44") (pinfunction "GNDBU_44") (pintype "passive"))
      (node (ref "U5") (pin "53") (pinfunction "GND_53") (pintype "passive"))
      (node (ref "U5") (pin "6") (pinfunction "GND_6") (pintype "passive"))
      (node (ref "U5") (pin "66") (pinfunction "GND_66") (pintype "passive"))
      (node (ref "U5") (pin "78") (pinfunction "GND_78") (pintype "passive"))
      (node (ref "U5") (pin "91") (pinfunction "GND_91") (pintype "passive"))
      (node (ref "U9") (pin "2") (pinfunction "GND_2") (pintype "passive"))
    )
    (net (code "16") (name "Net-(C144-Pad2)") (class "Default")
      (node (ref "C144") (pin "2") (pinfunction "2_2") (pintype "passive"))
      (node (ref "C145") (pin "2") (pinfunction "2_2") (pintype "passive"))
      (node (ref "C146") (pin "2") (pinfunction "2_2") (pintype "passive"))
      (node (ref "C147") (pin "2") (pinfunction "2_2") (pintype "passive"))
      (node (ref "C148") (pin "2") (pinfunction "2_2") (pintype "passive"))
      (node (ref "L26") (pin "2") (pinfunction "2_2") (pintype "passive"))
      (node (ref "U5") (pin "148") (pinfunction "VDDPLL_148") (pintype "passive"))
      (node (ref "U5") (pin "155") (pinfunction "VDDPLL_155") (pintype "passive"))
    )
    (net (code "17") (name "Net-(Q7-D)") (class "Default")
      (node (ref "Q7") (pin "3") (pinfunction "D_3") (pintype "passive"))
      (node (ref "R119") (pin "1") (pinfunction "1_1") (pintype "passive"))
    )
    (net (code "18") (name "Net-(Q12-D)") (class "Default")
      (node (ref "Q12") (pin "3") (pinfunction "D_3") (pintype "passive"))
      (node (ref "R158") (pin "1") (pinfunction "1_1") (pintype "passive"))
    )
    (net (code "19") (name "Net-(R158-Pad2)") (class "Default")
      (node (ref "R158") (pin "2") (pinfunction "2_2") (pintype "passive"))
      (node (ref "R160") (pin "1") (pinfunction "1_1") (pintype "passive"))
    )
    (net (code "20") (name "Net-(U1-EN)") (class "Default")
      (node (ref "R153") (pin "2") (pinfunction "2_2") (pintype "passive"))
      (node (ref "R154") (pin "1") (pinfunction "1_1") (pintype "passive"))
      (node (ref "U1") (pin "3") (pinfunction "EN_3") (pintype "passive"))
    )
    (net (code "21") (name "Net-(U1-FB)") (class "Default")
      (node (ref "R5") (pin "2") (pinfunction "2_2") (pintype "passive"))
      (node (ref "R6") (pin "2") (pinfunction "2_2") (pintype "passive"))
      (node (ref "U1") (pin "4") (pinfunction "FB_4") (pintype "passive"))
    )
    (net (code "22") (name "Net-(U1-SW)") (class "Default")
      (node (ref "L4") (pin "1") (pinfunction "1_1") (pintype "passive"))
      (node (ref "U1") (pin "5") (pinfunction "SW_5") (pintype "passive"))
    )
    (net (code "23") (name "Net-(U9-FB)") (class "Default")
      (node (ref "R8") (pin "2") (pinfunction "2_2") (pintype "passive"))
      (node (ref "R9") (pin "2") (pinfunction "2_2") (pintype "passive"))
      (node (ref "U9") (pin "4") (pinfunction "FB_4") (pintype "passive"))
    )
    (net (code "24") (name "Net-(U9-SW)") (class "Default")
      (node (ref "L5") (pin "1") (pinfunction "1_1") (pintype "passive"))
      (node (ref "U9") (pin "5") (pinfunction "SW_5") (pintype "passive"))
    )
    (net (code "25") (name "Net-(U14D-VDDA)") (class "Default")
      (node (ref "C167") (pin "2") (pinfunction "2_2") (pintype "passive"))
      (node (ref "C168") (pin "2") (pinfunction "2_2") (pintype "passive"))
      (node (ref "L29") (pin "2") (pinfunction "2_2") (pintype "passive"))
      (node (ref "U14") (pin "10") (pinfunction "VDDA_10") (pintype "power_in"))
      (node (ref "U14") (pin "12") (pinfunction "VREF_12") (pintype "input"))
    )
    (net (code "26") (name "Net-(U19-FB)") (class "Default")
      (node (ref "R113") (pin "1") (pinfunction "1_1") (pintype "passive"))
      (node (ref "R114") (pin "2") (pinfunction "2_2") (pintype "passive"))
      (node (ref "U19") (pin "3") (pinfunction "FB_3") (pintype "passive"))
    )
    (net (code "27") (name "Net-(U19-SW)") (class "Default")
      (node (ref "L3") (pin "1") (pinfunction "1_1") (pintype "passive"))
      (node (ref "U19") (pin "7") (pinfunction "SW_7") (pintype "passive"))
    )
    (net (code "28") (name "Net-(U20-EN)") (class "Default")
      (node (ref "C18") (pin "2") (pinfunction "2_2") (pintype "passive"))
      (node (ref "L7") (pin "1") (pinfunction "1_1") (pintype "passive"))
      (node (ref "U20") (pin "1") (pinfunction "IN_1") (pintype "passive"))
      (node (ref "U20") (pin "3") (pinfunction "EN_3") (pintype "passive"))
    )
    (net (code "29") (name "Net-(U22-FB)") (class "Default")
      (node (ref "C163") (pin "2") (pinfunction "2_2") (pintype "passive"))
      (node (ref "U22") (pin "6") (pinfunction "VO_TAP_6") (pintype "passive"))
      (node (ref "U22") (pin "7") (pinfunction "FB_7") (pintype "input"))
    )
    (net (code "30") (name "Net-(U23-GP1{slash}AN1{slash}CIN-{slash}VREF{slash}ICSPCLK)") (class "Default")
      (node (ref "R159") (pin "2") (pinfunction "2_2") (pintype "passive"))
      (node (ref "U23") (pin "6") (pinfunction "GP1/AN1/CIN-/VREF/ICSPCLK_6") (pintype "bidirectional"))
    )
    (net (code "31") (name "Net-(U23-GP5{slash}T1CKI{slash}OSC1{slash}CLKIN)") (class "Default")
      (node (ref "R122") (pin "1") (pinfunction "1_1") (pintype "passive"))
      (node (ref "U23") (pin "2") (pinfunction "GP5/T1CKI/OSC1/CLKIN_2") (pintype "bidirectional"))
    )
    (net (code "32") (name "Net-(U23-VDD)") (class "Default")
      (node (ref "C220") (pin "2") (pinfunction "2_2") (pintype "passive"))
      (node (ref "R156") (pin "1") (pinfunction "1_1") (pintype "passive"))
      (node (ref "R157") (pin "1") (pinfunction "1_1") (pintype "passive"))
      (node (ref "U23") (pin "1") (pinfunction "VDD_1") (pintype "power_in"))
    )
    (net (code "33") (name "RFIN_GND") (class "Default")
      (node (ref "C15") (pin "2") (pinfunction "2_2") (pintype "passive"))
      (node (ref "C16") (pin "2") (pinfunction "2_2") (pintype "passive"))
      (node (ref "C18") (pin "1") (pinfunction "1_1") (pintype "passive"))
      (node (ref "U20") (pin "2") (pinfunction "GND_2") (pintype "passive"))
    )
    (net (code "34") (name "unconnected-(U5D-NC-Pad152)") (class "Default")
      (node (ref "U5") (pin "152") (pinfunction "NC_152") (pintype "passive+no_connect"))
    )
    (net (code "35") (name "unconnected-(U14D-NC-Pad13)") (class "Default")
      (node (ref "U14") (pin "13") (pinfunction "NC_13") (pintype "power_in+no_connect"))
    )
    (net (code "36") (name "unconnected-(U22-~{ERR}-Pad5)") (class "Default")
      (node (ref "U22") (pin "5") (pinfunction "~{ERR}_5") (pintype "open_collector+no_connect"))
    )
  )
)
